# Freezer.net
KiCad netlist of a schematic drawn in EAGLE
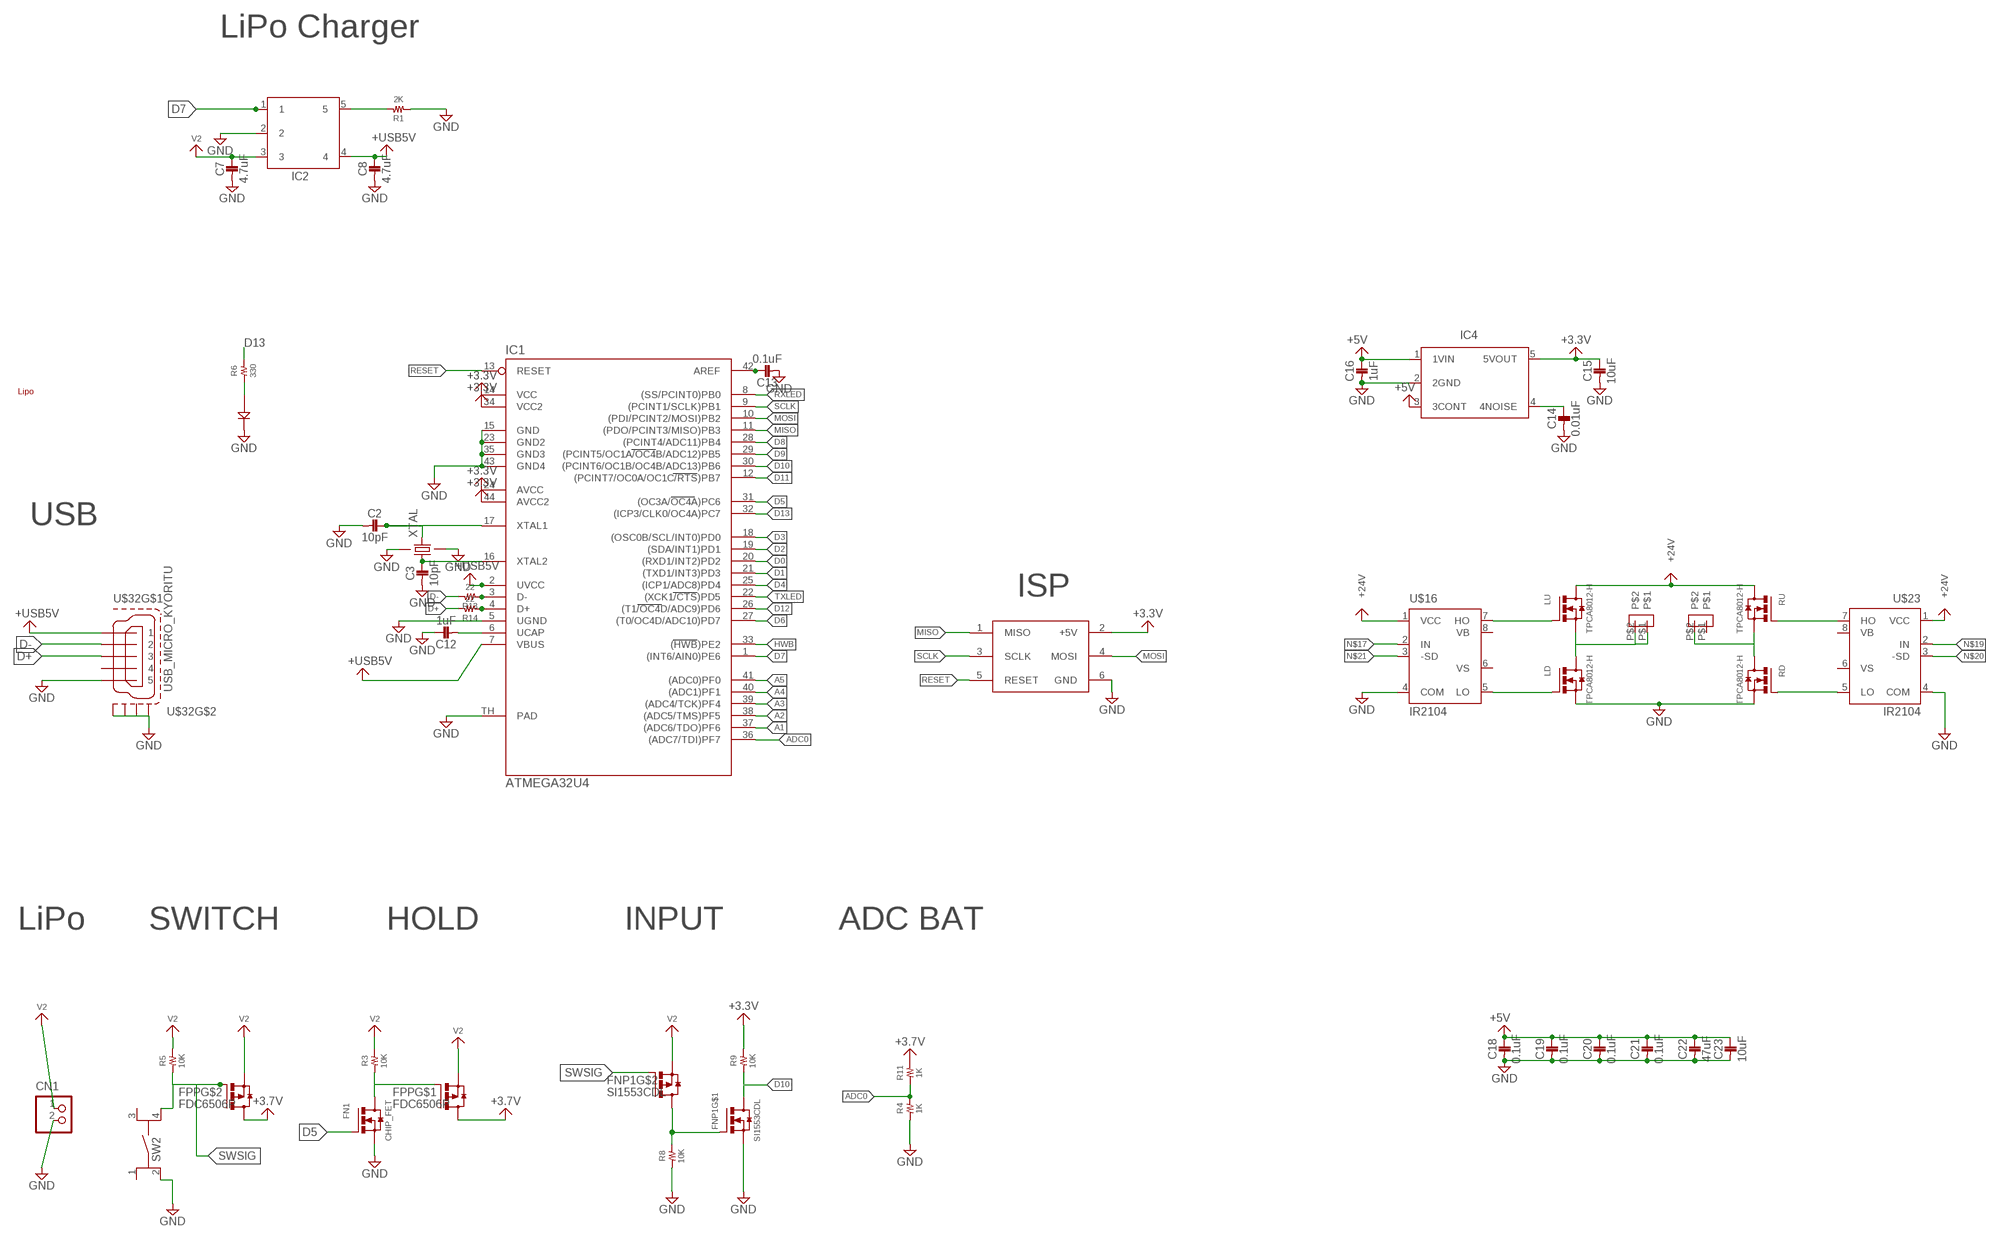
[diagram p0: schematic, sheet 1]

(export (version "E")
  (design (tool "Eeschema 10.0.6"))
  (components
    (comp (ref "C2")
      (value "10pF")
      (footprint "eagle-import:1005")
      (libsource (lib "eagle-import") (part "1005"))
    )
    (comp (ref "C3")
      (value "10pF")
      (footprint "eagle-import:1005")
      (libsource (lib "eagle-import") (part "1005"))
    )
    (comp (ref "C7")
      (value "4.7uF")
      (footprint "eagle-import:1005")
      (libsource (lib "eagle-import") (part "1005"))
    )
    (comp (ref "C8")
      (value "4.7uF")
      (footprint "eagle-import:1005")
      (libsource (lib "eagle-import") (part "1005"))
    )
    (comp (ref "C12")
      (value "1uF")
      (footprint "eagle-import:1005")
      (libsource (lib "eagle-import") (part "1005"))
    )
    (comp (ref "C13")
      (value "0.1uF")
      (footprint "eagle-import:1005")
      (libsource (lib "eagle-import") (part "1005"))
    )
    (comp (ref "C14")
      (value "0.01uF")
      (footprint "eagle-import:1608")
      (libsource (lib "eagle-import") (part "1608"))
    )
    (comp (ref "C15")
      (value "10uF")
      (footprint "eagle-import:1608")
      (libsource (lib "eagle-import") (part "1608"))
    )
    (comp (ref "C16")
      (value "1uF")
      (footprint "eagle-import:1005")
      (libsource (lib "eagle-import") (part "1005"))
    )
    (comp (ref "C18")
      (value "0.1uF")
      (footprint "eagle-import:1005")
      (libsource (lib "eagle-import") (part "1005"))
    )
    (comp (ref "C19")
      (value "0.1uF")
      (footprint "eagle-import:1005")
      (libsource (lib "eagle-import") (part "1005"))
    )
    (comp (ref "C20")
      (value "0.1uF")
      (footprint "eagle-import:1005")
      (libsource (lib "eagle-import") (part "1005"))
    )
    (comp (ref "C21")
      (value "0.1uF")
      (footprint "eagle-import:1005")
      (libsource (lib "eagle-import") (part "1005"))
    )
    (comp (ref "C22")
      (value "47uF")
      (footprint "eagle-import:1608")
      (libsource (lib "eagle-import") (part "1608"))
    )
    (comp (ref "C23")
      (value "10uF")
      (footprint "eagle-import:1608")
      (libsource (lib "eagle-import") (part "1608"))
    )
    (comp (ref "CN1")
      (value "S2B-PH-K-S")
      (footprint "eagle-import:S2B-PH-K-S")
      (libsource (lib "eagle-import") (part "S2B-PH-K-S"))
    )
    (comp (ref "FN1")
      (value "CHIP_FET")
      (footprint "eagle-import:SOT23")
      (libsource (lib "eagle-import") (part "CHIP_FET"))
    )
    (comp (ref "FNP1")
      (value "SI1553CDL")
      (footprint "eagle-import:SOT363")
      (libsource (lib "eagle-import") (part "SI1553CDL"))
    )
    (comp (ref "FPP")
      (value "FDC6506P")
      (footprint "eagle-import:SOT23-6")
      (libsource (lib "eagle-import") (part "FDC6506P"))
    )
    (comp (ref "IC1")
      (value "ATMEGA32U4")
      (footprint "eagle-import:QFN-44-7X7")
      (libsource (lib "eagle-import") (part "ATMEGA32U4"))
    )
    (comp (ref "IC2")
      (value "MCP73831")
      (footprint "eagle-import:SOT23-5L")
      (libsource (lib "eagle-import") (part "MCP73831"))
    )
    (comp (ref "IC4")
      (value "TAR5SB")
      (footprint "eagle-import:SSOP5-P-0.95")
      (libsource (lib "eagle-import") (part "TAR5SB"))
    )
    (comp (ref "LD")
      (value "TPCA8012-H")
      (footprint "eagle-import:2-5Q1A")
      (libsource (lib "eagle-import") (part "TPCA8012-H"))
    )
    (comp (ref "LED1")
      (value "1608")
      (footprint "eagle-import:1608")
      (libsource (lib "eagle-import") (part "10_LED_1608"))
    )
    (comp (ref "LU")
      (value "TPCA8012-H")
      (footprint "eagle-import:2-5Q1A")
      (libsource (lib "eagle-import") (part "TPCA8012-H"))
    )
    (comp (ref "R1")
      (value "2K")
      (footprint "eagle-import:1005")
      (libsource (lib "eagle-import") (part "RESISTOR_1005"))
    )
    (comp (ref "R3")
      (value "10K")
      (footprint "eagle-import:1005")
      (libsource (lib "eagle-import") (part "RESISTOR_1005"))
    )
    (comp (ref "R4")
      (value "1K")
      (footprint "eagle-import:1005")
      (libsource (lib "eagle-import") (part "RESISTOR_1005"))
    )
    (comp (ref "R5")
      (value "10K")
      (footprint "eagle-import:1005")
      (libsource (lib "eagle-import") (part "RESISTOR_1005"))
    )
    (comp (ref "R6")
      (value "330")
      (footprint "eagle-import:1005")
      (libsource (lib "eagle-import") (part "RESISTOR_1005"))
    )
    (comp (ref "R8")
      (value "10K")
      (footprint "eagle-import:1005")
      (libsource (lib "eagle-import") (part "RESISTOR_1005"))
    )
    (comp (ref "R9")
      (value "10K")
      (footprint "eagle-import:1005")
      (libsource (lib "eagle-import") (part "RESISTOR_1005"))
    )
    (comp (ref "R11")
      (value "1K")
      (footprint "eagle-import:1005")
      (libsource (lib "eagle-import") (part "RESISTOR_1005"))
    )
    (comp (ref "R13")
      (value "22")
      (footprint "eagle-import:1005")
      (libsource (lib "eagle-import") (part "RESISTOR_1005"))
    )
    (comp (ref "R14")
      (value "22")
      (footprint "eagle-import:1005")
      (libsource (lib "eagle-import") (part "RESISTOR_1005"))
    )
    (comp (ref "RD")
      (value "TPCA8012-H")
      (footprint "eagle-import:2-5Q1A")
      (libsource (lib "eagle-import") (part "TPCA8012-H"))
    )
    (comp (ref "RU")
      (value "TPCA8012-H")
      (footprint "eagle-import:2-5Q1A")
      (libsource (lib "eagle-import") (part "TPCA8012-H"))
    )
    (comp (ref "SW2")
      (value "SKRPACE010")
      (footprint "eagle-import:SKRP")
      (libsource (lib "eagle-import") (part "SKRPACE010"))
    )
    (comp (ref "U$3")
      (value "ICSP")
      (footprint "eagle-import:ICSP")
      (libsource (lib "eagle-import") (part "ICSP"))
    )
    (comp (ref "U$16")
      (value "IR2104")
      (footprint "eagle-import:SOIC8")
      (libsource (lib "eagle-import") (part "IR2104"))
    )
    (comp (ref "U$23")
      (value "IR2104")
      (footprint "eagle-import:SOIC8")
      (libsource (lib "eagle-import") (part "IR2104"))
    )
    (comp (ref "U$32")
      (value "USB_MICRO_KYORITU")
      (footprint "eagle-import:USB_MICRO_KYORITU")
      (libsource (lib "eagle-import") (part "USB_MICRO_KYORITU"))
    )
    (comp (ref "U$38")
      (value "TERMINAL_2P")
      (footprint "eagle-import:TERMINAL_2P")
      (libsource (lib "eagle-import") (part "TERMINAL_2P"))
    )
    (comp (ref "U$43")
      (value "TERMINAL_2P")
      (footprint "eagle-import:TERMINAL_2P")
      (libsource (lib "eagle-import") (part "TERMINAL_2P"))
    )
    (comp (ref "U$68")
      (value "LIPO500MAH")
      (footprint "eagle-import:LIPO500MAH")
      (libsource (lib "eagle-import") (part "LIPO500MAH"))
    )
    (comp (ref "XTAL")
      (value "FA-238")
      (footprint "eagle-import:FA-238")
      (libsource (lib "eagle-import") (part "FA-238"))
    )
  )
  (nets
    (net (code "1") (name "+3.3V") (class "Default")
      (node (ref "C15") (pin "P$1") (pinfunction "1_P$1") (pintype "passive"))
      (node (ref "IC1") (pin "14") (pinfunction "VCC_14") (pintype "bidirectional"))
      (node (ref "IC1") (pin "24") (pinfunction "AVCC_24") (pintype "bidirectional"))
      (node (ref "IC1") (pin "34") (pinfunction "VCC2_34") (pintype "bidirectional"))
      (node (ref "IC1") (pin "44") (pinfunction "AVCC2_44") (pintype "bidirectional"))
      (node (ref "IC4") (pin "5") (pinfunction "5VOUT_5") (pintype "bidirectional"))
      (node (ref "R9") (pin "2") (pinfunction "P$2_2") (pintype "passive"))
      (node (ref "U$3") (pin "2") (pinfunction "+5V_2") (pintype "bidirectional"))
    )
    (net (code "2") (name "+3.7V") (class "Default")
      (node (ref "FPP") (pin "4") (pinfunction "D_4") (pintype "passive"))
      (node (ref "FPP") (pin "6") (pinfunction "D_6") (pintype "passive"))
      (node (ref "R11") (pin "2") (pinfunction "P$2_2") (pintype "passive"))
    )
    (net (code "3") (name "+5V") (class "Default")
      (node (ref "C16") (pin "1") (pinfunction "1_1") (pintype "passive"))
      (node (ref "C18") (pin "1") (pinfunction "1_1") (pintype "passive"))
      (node (ref "C19") (pin "1") (pinfunction "1_1") (pintype "passive"))
      (node (ref "C20") (pin "1") (pinfunction "1_1") (pintype "passive"))
      (node (ref "C21") (pin "1") (pinfunction "1_1") (pintype "passive"))
      (node (ref "C22") (pin "P$1") (pinfunction "1_P$1") (pintype "passive"))
      (node (ref "C23") (pin "P$1") (pinfunction "1_P$1") (pintype "passive"))
      (node (ref "IC4") (pin "1") (pinfunction "1VIN_1") (pintype "bidirectional"))
      (node (ref "IC4") (pin "3") (pinfunction "3CONT_3") (pintype "bidirectional"))
    )
    (net (code "4") (name "+24V") (class "Default")
      (node (ref "LU") (pin "5") (pinfunction "D_5") (pintype "passive"))
      (node (ref "LU") (pin "6") (pinfunction "D_6") (pintype "passive"))
      (node (ref "LU") (pin "7") (pinfunction "D_7") (pintype "passive"))
      (node (ref "LU") (pin "8") (pinfunction "D_8") (pintype "passive"))
      (node (ref "RU") (pin "5") (pinfunction "D_5") (pintype "passive"))
      (node (ref "RU") (pin "6") (pinfunction "D_6") (pintype "passive"))
      (node (ref "RU") (pin "7") (pinfunction "D_7") (pintype "passive"))
      (node (ref "RU") (pin "8") (pinfunction "D_8") (pintype "passive"))
      (node (ref "U$16") (pin "1") (pinfunction "VCC_1") (pintype "power_in"))
      (node (ref "U$23") (pin "1") (pinfunction "VCC_1") (pintype "power_in"))
    )
    (net (code "5") (name "+USB5V") (class "Default")
      (node (ref "C8") (pin "1") (pinfunction "1_1") (pintype "passive"))
      (node (ref "IC1") (pin "2") (pinfunction "UVCC_2") (pintype "bidirectional"))
      (node (ref "IC1") (pin "7") (pinfunction "VBUS_7") (pintype "bidirectional"))
      (node (ref "IC2") (pin "4") (pinfunction "4_4") (pintype "bidirectional"))
      (node (ref "U$32") (pin "1") (pinfunction "1_1") (pintype "input"))
    )
    (net (code "6") (name "A1") (class "Default")
      (node (ref "IC1") (pin "37") (pinfunction "(ADC6/TDO)PF6_37") (pintype "bidirectional"))
    )
    (net (code "7") (name "A2") (class "Default")
      (node (ref "IC1") (pin "38") (pinfunction "(ADC5/TMS)PF5_38") (pintype "bidirectional"))
    )
    (net (code "8") (name "A3") (class "Default")
      (node (ref "IC1") (pin "39") (pinfunction "(ADC4/TCK)PF4_39") (pintype "bidirectional"))
    )
    (net (code "9") (name "A4") (class "Default")
      (node (ref "IC1") (pin "40") (pinfunction "(ADC1)PF1_40") (pintype "bidirectional"))
    )
    (net (code "10") (name "A5") (class "Default")
      (node (ref "IC1") (pin "41") (pinfunction "(ADC0)PF0_41") (pintype "bidirectional"))
    )
    (net (code "11") (name "ADC0") (class "Default")
      (node (ref "IC1") (pin "36") (pinfunction "(ADC7/TDI)PF7_36") (pintype "bidirectional"))
      (node (ref "R11") (pin "1") (pinfunction "P$1_1") (pintype "passive"))
      (node (ref "R4") (pin "2") (pinfunction "P$2_2") (pintype "passive"))
    )
    (net (code "12") (name "D+") (class "Default")
      (node (ref "R14") (pin "2") (pinfunction "P$2_2") (pintype "passive"))
      (node (ref "U$32") (pin "3") (pinfunction "3_3") (pintype "input"))
    )
    (net (code "13") (name "D-") (class "Default")
      (node (ref "R13") (pin "2") (pinfunction "P$2_2") (pintype "passive"))
      (node (ref "U$32") (pin "2") (pinfunction "2_2") (pintype "input"))
    )
    (net (code "14") (name "D0") (class "Default")
      (node (ref "IC1") (pin "20") (pinfunction "(RXD1/INT2)PD2_20") (pintype "bidirectional"))
    )
    (net (code "15") (name "D1") (class "Default")
      (node (ref "IC1") (pin "21") (pinfunction "(TXD1/INT3)PD3_21") (pintype "bidirectional"))
    )
    (net (code "16") (name "D2") (class "Default")
      (node (ref "IC1") (pin "19") (pinfunction "(SDA/INT1)PD1_19") (pintype "bidirectional"))
    )
    (net (code "17") (name "D3") (class "Default")
      (node (ref "IC1") (pin "18") (pinfunction "(OSC0B/SCL/INT0)PD0_18") (pintype "bidirectional"))
    )
    (net (code "18") (name "D4") (class "Default")
      (node (ref "IC1") (pin "25") (pinfunction "(ICP1/ADC8)PD4_25") (pintype "bidirectional"))
    )
    (net (code "19") (name "D5") (class "Default")
      (node (ref "FN1") (pin "1") (pinfunction "G_1") (pintype "passive"))
      (node (ref "IC1") (pin "31") (pinfunction "(OC3A/OC4A)PC6_31") (pintype "bidirectional"))
    )
    (net (code "20") (name "D6") (class "Default")
      (node (ref "IC1") (pin "27") (pinfunction "(T0/OC4D/ADC10)PD7_27") (pintype "bidirectional"))
    )
    (net (code "21") (name "D7") (class "Default")
      (node (ref "IC1") (pin "1") (pinfunction "(INT6/AIN0)PE6_1") (pintype "bidirectional"))
      (node (ref "IC2") (pin "1") (pinfunction "1_1") (pintype "bidirectional"))
    )
    (net (code "22") (name "D8") (class "Default")
      (node (ref "IC1") (pin "28") (pinfunction "(PCINT4/ADC11)PB4_28") (pintype "bidirectional"))
    )
    (net (code "23") (name "D9") (class "Default")
      (node (ref "IC1") (pin "29") (pinfunction "(PCINT5/OC1A/OC4B/ADC12)PB5_29") (pintype "bidirectional"))
    )
    (net (code "24") (name "D10") (class "Default")
      (node (ref "FNP1") (pin "6") (pinfunction "D_6") (pintype "passive"))
      (node (ref "IC1") (pin "30") (pinfunction "(PCINT6/OC1B/OC4B/ADC13)PB6_30") (pintype "bidirectional"))
      (node (ref "R9") (pin "1") (pinfunction "P$1_1") (pintype "passive"))
    )
    (net (code "25") (name "D11") (class "Default")
      (node (ref "IC1") (pin "12") (pinfunction "(PCINT7/OC0A/OC1C/RTS)PB7_12") (pintype "bidirectional"))
    )
    (net (code "26") (name "D12") (class "Default")
      (node (ref "IC1") (pin "26") (pinfunction "(T1/OC4D/ADC9)PD6_26") (pintype "bidirectional"))
    )
    (net (code "27") (name "D13") (class "Default")
      (node (ref "IC1") (pin "32") (pinfunction "(ICP3/CLK0/OC4A)PC7_32") (pintype "bidirectional"))
      (node (ref "R6") (pin "2") (pinfunction "P$2_2") (pintype "passive"))
    )
    (net (code "28") (name "GND") (class "Default")
      (node (ref "C12") (pin "1") (pinfunction "1_1") (pintype "passive"))
      (node (ref "C13") (pin "2") (pinfunction "2_2") (pintype "passive"))
      (node (ref "C14") (pin "P$2") (pinfunction "2_P$2") (pintype "passive"))
      (node (ref "C15") (pin "P$2") (pinfunction "2_P$2") (pintype "passive"))
      (node (ref "C16") (pin "2") (pinfunction "2_2") (pintype "passive"))
      (node (ref "C18") (pin "2") (pinfunction "2_2") (pintype "passive"))
      (node (ref "C19") (pin "2") (pinfunction "2_2") (pintype "passive"))
      (node (ref "C2") (pin "2") (pinfunction "2_2") (pintype "passive"))
      (node (ref "C20") (pin "2") (pinfunction "2_2") (pintype "passive"))
      (node (ref "C21") (pin "2") (pinfunction "2_2") (pintype "passive"))
      (node (ref "C22") (pin "P$2") (pinfunction "2_P$2") (pintype "passive"))
      (node (ref "C23") (pin "P$2") (pinfunction "2_P$2") (pintype "passive"))
      (node (ref "C3") (pin "2") (pinfunction "2_2") (pintype "passive"))
      (node (ref "C7") (pin "2") (pinfunction "2_2") (pintype "passive"))
      (node (ref "C8") (pin "2") (pinfunction "2_2") (pintype "passive"))
      (node (ref "CN1") (pin "2") (pinfunction "2_2") (pintype "passive"))
      (node (ref "FN1") (pin "2") (pinfunction "S_2") (pintype "passive"))
      (node (ref "FNP1") (pin "1") (pinfunction "S_1") (pintype "passive"))
      (node (ref "IC1") (pin "15") (pinfunction "GND_15") (pintype "bidirectional"))
      (node (ref "IC1") (pin "23") (pinfunction "GND2_23") (pintype "bidirectional"))
      (node (ref "IC1") (pin "35") (pinfunction "GND3_35") (pintype "bidirectional"))
      (node (ref "IC1") (pin "43") (pinfunction "GND4_43") (pintype "bidirectional"))
      (node (ref "IC1") (pin "5") (pinfunction "UGND_5") (pintype "bidirectional"))
      (node (ref "IC1") (pin "TH") (pinfunction "PAD_TH") (pintype "bidirectional"))
      (node (ref "IC2") (pin "2") (pinfunction "2_2") (pintype "bidirectional"))
      (node (ref "IC4") (pin "2") (pinfunction "2GND_2") (pintype "bidirectional"))
      (node (ref "LD") (pin "1") (pinfunction "S_1") (pintype "passive"))
      (node (ref "LD") (pin "2") (pinfunction "S_2") (pintype "passive"))
      (node (ref "LD") (pin "3") (pinfunction "S_3") (pintype "passive"))
      (node (ref "LED1") (pin "2") (pinfunction "K_2") (pintype "bidirectional"))
      (node (ref "R1") (pin "1") (pinfunction "P$1_1") (pintype "passive"))
      (node (ref "R4") (pin "1") (pinfunction "P$1_1") (pintype "passive"))
      (node (ref "R8") (pin "1") (pinfunction "P$1_1") (pintype "passive"))
      (node (ref "RD") (pin "1") (pinfunction "S_1") (pintype "passive"))
      (node (ref "RD") (pin "2") (pinfunction "S_2") (pintype "passive"))
      (node (ref "RD") (pin "3") (pinfunction "S_3") (pintype "passive"))
      (node (ref "SW2") (pin "2") (pinfunction "1__2") (pintype "passive"))
      (node (ref "U$16") (pin "4") (pinfunction "COM_4") (pintype "power_in"))
      (node (ref "U$23") (pin "4") (pinfunction "COM_4") (pintype "power_in"))
      (node (ref "U$3") (pin "6") (pinfunction "GND_6") (pintype "bidirectional"))
      (node (ref "U$32") (pin "5") (pinfunction "5_5") (pintype "input"))
      (node (ref "U$32") (pin "M1") (pinfunction "S1_M1") (pintype "passive"))
      (node (ref "U$32") (pin "M2") (pinfunction "S2_M2") (pintype "passive"))
      (node (ref "U$32") (pin "M3") (pinfunction "S3_M3") (pintype "passive"))
      (node (ref "U$32") (pin "M4") (pinfunction "S4_M4") (pintype "passive"))
      (node (ref "XTAL") (pin "2") (pinfunction "2_2") (pintype "bidirectional"))
      (node (ref "XTAL") (pin "4") (pinfunction "4_4") (pintype "bidirectional"))
    )
    (net (code "29") (name "HWB") (class "Default")
      (node (ref "IC1") (pin "33") (pinfunction "(HWB)PE2_33") (pintype "bidirectional"))
    )
    (net (code "30") (name "MISO") (class "Default")
      (node (ref "IC1") (pin "11") (pinfunction "(PDO/PCINT3/MISO)PB3_11") (pintype "bidirectional"))
      (node (ref "U$3") (pin "1") (pinfunction "MISO_1") (pintype "bidirectional"))
    )
    (net (code "31") (name "MOSI") (class "Default")
      (node (ref "IC1") (pin "10") (pinfunction "(PDI/PCINT2/MOSI)PB2_10") (pintype "bidirectional"))
      (node (ref "U$3") (pin "4") (pinfunction "MOSI_4") (pintype "bidirectional"))
    )
    (net (code "32") (name "N$17") (class "Default")
      (node (ref "U$16") (pin "2") (pinfunction "IN_2") (pintype "input"))
    )
    (net (code "33") (name "N$19") (class "Default")
      (node (ref "U$23") (pin "2") (pinfunction "IN_2") (pintype "input"))
    )
    (net (code "34") (name "N$20") (class "Default")
      (node (ref "U$23") (pin "3") (pinfunction "-SD_3") (pintype "input"))
    )
    (net (code "35") (name "N$21") (class "Default")
      (node (ref "U$16") (pin "3") (pinfunction "-SD_3") (pintype "input"))
    )
    (net (code "36") (name "Net-(C14-1)") (class "Default")
      (node (ref "C14") (pin "P$1") (pinfunction "1_P$1") (pintype "passive"))
      (node (ref "IC4") (pin "4") (pinfunction "4NOISE_4") (pintype "bidirectional"))
    )
    (net (code "37") (name "Net-(FN1-D)") (class "Default")
      (node (ref "FN1") (pin "3") (pinfunction "D_3") (pintype "passive"))
      (node (ref "FPP") (pin "1") (pinfunction "G_1") (pintype "passive"))
      (node (ref "R3") (pin "1") (pinfunction "P$1_1") (pintype "passive"))
    )
    (net (code "38") (name "Net-(FNP1A-G)") (class "Default")
      (node (ref "FNP1") (pin "2") (pinfunction "G_2") (pintype "passive"))
      (node (ref "FNP1") (pin "3") (pinfunction "D_3") (pintype "passive"))
      (node (ref "R8") (pin "2") (pinfunction "P$2_2") (pintype "passive"))
    )
    (net (code "39") (name "Net-(IC1-AREF)") (class "Default")
      (node (ref "C13") (pin "1") (pinfunction "1_1") (pintype "passive"))
      (node (ref "IC1") (pin "42") (pinfunction "AREF_42") (pintype "bidirectional"))
    )
    (net (code "40") (name "Net-(IC1-D+)") (class "Default")
      (node (ref "IC1") (pin "4") (pinfunction "D+_4") (pintype "bidirectional"))
      (node (ref "R14") (pin "1") (pinfunction "P$1_1") (pintype "passive"))
    )
    (net (code "41") (name "Net-(IC1-D-)") (class "Default")
      (node (ref "IC1") (pin "3") (pinfunction "D-_3") (pintype "bidirectional"))
      (node (ref "R13") (pin "1") (pinfunction "P$1_1") (pintype "passive"))
    )
    (net (code "42") (name "Net-(IC1-UCAP)") (class "Default")
      (node (ref "C12") (pin "2") (pinfunction "2_2") (pintype "passive"))
      (node (ref "IC1") (pin "6") (pinfunction "UCAP_6") (pintype "bidirectional"))
    )
    (net (code "43") (name "Net-(IC1-XTAL1)") (class "Default")
      (node (ref "C2") (pin "1") (pinfunction "1_1") (pintype "passive"))
      (node (ref "IC1") (pin "17") (pinfunction "XTAL1_17") (pintype "bidirectional"))
      (node (ref "XTAL") (pin "3") (pinfunction "3_3") (pintype "passive"))
    )
    (net (code "44") (name "Net-(IC1-XTAL2)") (class "Default")
      (node (ref "C3") (pin "1") (pinfunction "1_1") (pintype "passive"))
      (node (ref "IC1") (pin "16") (pinfunction "XTAL2_16") (pintype "bidirectional"))
      (node (ref "XTAL") (pin "1") (pinfunction "1_1") (pintype "passive"))
    )
    (net (code "45") (name "Net-(LD-D-Pad5)") (class "Default")
      (node (ref "LD") (pin "5") (pinfunction "D_5") (pintype "passive"))
      (node (ref "LD") (pin "6") (pinfunction "D_6") (pintype "passive"))
      (node (ref "LD") (pin "7") (pinfunction "D_7") (pintype "passive"))
      (node (ref "LD") (pin "8") (pinfunction "D_8") (pintype "passive"))
      (node (ref "LU") (pin "1") (pinfunction "S_1") (pintype "passive"))
      (node (ref "LU") (pin "2") (pinfunction "S_2") (pintype "passive"))
      (node (ref "LU") (pin "3") (pinfunction "S_3") (pintype "passive"))
      (node (ref "U$38") (pin "P$1") (pinfunction "P$1_P$1") (pintype "bidirectional"))
      (node (ref "U$38") (pin "P$2") (pinfunction "P$2_P$2") (pintype "bidirectional"))
    )
    (net (code "46") (name "Net-(LD-G)") (class "Default")
      (node (ref "LD") (pin "4") (pinfunction "G_4") (pintype "passive"))
      (node (ref "U$16") (pin "5") (pinfunction "LO_5") (pintype "output"))
    )
    (net (code "47") (name "Net-(LED1-A)") (class "Default")
      (node (ref "LED1") (pin "1") (pinfunction "A_1") (pintype "bidirectional"))
      (node (ref "R6") (pin "1") (pinfunction "P$1_1") (pintype "passive"))
    )
    (net (code "48") (name "Net-(LU-G)") (class "Default")
      (node (ref "LU") (pin "4") (pinfunction "G_4") (pintype "passive"))
      (node (ref "U$16") (pin "7") (pinfunction "HO_7") (pintype "output"))
    )
    (net (code "49") (name "Net-(R1-P$2)") (class "Default")
      (node (ref "IC2") (pin "5") (pinfunction "5_5") (pintype "bidirectional"))
      (node (ref "R1") (pin "2") (pinfunction "P$2_2") (pintype "passive"))
    )
    (net (code "50") (name "Net-(RD-D-Pad5)") (class "Default")
      (node (ref "RD") (pin "5") (pinfunction "D_5") (pintype "passive"))
      (node (ref "RD") (pin "6") (pinfunction "D_6") (pintype "passive"))
      (node (ref "RD") (pin "7") (pinfunction "D_7") (pintype "passive"))
      (node (ref "RD") (pin "8") (pinfunction "D_8") (pintype "passive"))
      (node (ref "RU") (pin "1") (pinfunction "S_1") (pintype "passive"))
      (node (ref "RU") (pin "2") (pinfunction "S_2") (pintype "passive"))
      (node (ref "RU") (pin "3") (pinfunction "S_3") (pintype "passive"))
      (node (ref "U$43") (pin "P$2") (pinfunction "P$2_P$2") (pintype "bidirectional"))
    )
    (net (code "51") (name "Net-(RD-G)") (class "Default")
      (node (ref "RD") (pin "4") (pinfunction "G_4") (pintype "passive"))
      (node (ref "U$23") (pin "5") (pinfunction "LO_5") (pintype "output"))
    )
    (net (code "52") (name "Net-(RU-G)") (class "Default")
      (node (ref "RU") (pin "4") (pinfunction "G_4") (pintype "passive"))
      (node (ref "U$23") (pin "7") (pinfunction "HO_7") (pintype "output"))
    )
    (net (code "53") (name "RESET") (class "Default")
      (node (ref "IC1") (pin "13") (pinfunction "RESET_13") (pintype "bidirectional"))
      (node (ref "U$3") (pin "5") (pinfunction "RESET_5") (pintype "bidirectional"))
    )
    (net (code "54") (name "RXLED") (class "Default")
      (node (ref "IC1") (pin "8") (pinfunction "(SS/PCINT0)PB0_8") (pintype "bidirectional"))
    )
    (net (code "55") (name "SCLK") (class "Default")
      (node (ref "IC1") (pin "9") (pinfunction "(PCINT1/SCLK)PB1_9") (pintype "bidirectional"))
      (node (ref "U$3") (pin "3") (pinfunction "SCLK_3") (pintype "bidirectional"))
    )
    (net (code "56") (name "SWSIG") (class "Default")
      (node (ref "FNP1") (pin "5") (pinfunction "G_5") (pintype "passive"))
      (node (ref "FPP") (pin "3") (pinfunction "G_3") (pintype "passive"))
      (node (ref "R5") (pin "1") (pinfunction "P$1_1") (pintype "passive"))
      (node (ref "SW2") (pin "4") (pinfunction "2__4") (pintype "passive"))
    )
    (net (code "57") (name "TXLED") (class "Default")
      (node (ref "IC1") (pin "22") (pinfunction "(XCK1/CTS)PD5_22") (pintype "bidirectional"))
    )
    (net (code "58") (name "V2") (class "Default")
      (node (ref "C7") (pin "1") (pinfunction "1_1") (pintype "passive"))
      (node (ref "CN1") (pin "1") (pinfunction "1_1") (pintype "passive"))
      (node (ref "FNP1") (pin "4") (pinfunction "S_4") (pintype "passive"))
      (node (ref "FPP") (pin "2") (pinfunction "S_2") (pintype "passive"))
      (node (ref "FPP") (pin "5") (pinfunction "S_5") (pintype "passive"))
      (node (ref "IC2") (pin "3") (pinfunction "3_3") (pintype "bidirectional"))
      (node (ref "R3") (pin "2") (pinfunction "P$2_2") (pintype "passive"))
      (node (ref "R5") (pin "2") (pinfunction "P$2_2") (pintype "passive"))
    )
    (net (code "59") (name "unconnected-(SW2-2-Pad3)") (class "Default")
      (node (ref "SW2") (pin "3") (pinfunction "2_3") (pintype "passive"))
    )
    (net (code "60") (name "unconnected-(SW2-Pad1)") (class "Default")
      (node (ref "SW2") (pin "1") (pinfunction "1_1") (pintype "passive"))
    )
    (net (code "61") (name "unconnected-(U$16-VB-Pad8)") (class "Default")
      (node (ref "U$16") (pin "8") (pinfunction "VB_8") (pintype "passive"))
    )
    (net (code "62") (name "unconnected-(U$16-VS-Pad6)") (class "Default")
      (node (ref "U$16") (pin "6") (pinfunction "VS_6") (pintype "input"))
    )
    (net (code "63") (name "unconnected-(U$23-VB-Pad8)") (class "Default")
      (node (ref "U$23") (pin "8") (pinfunction "VB_8") (pintype "passive"))
    )
    (net (code "64") (name "unconnected-(U$23-VS-Pad6)") (class "Default")
      (node (ref "U$23") (pin "6") (pinfunction "VS_6") (pintype "input"))
    )
    (net (code "65") (name "unconnected-(U$32-Pad4)") (class "Default")
      (node (ref "U$32") (pin "4") (pinfunction "4_4") (pintype "input"))
    )
    (net (code "66") (name "unconnected-(U$43-PadP$1)") (class "Default")
      (node (ref "U$43") (pin "P$1") (pinfunction "P$1_P$1") (pintype "bidirectional"))
    )
  )
)
